# SX1268.net
KiCad netlist of a schematic drawn in Altium Designer
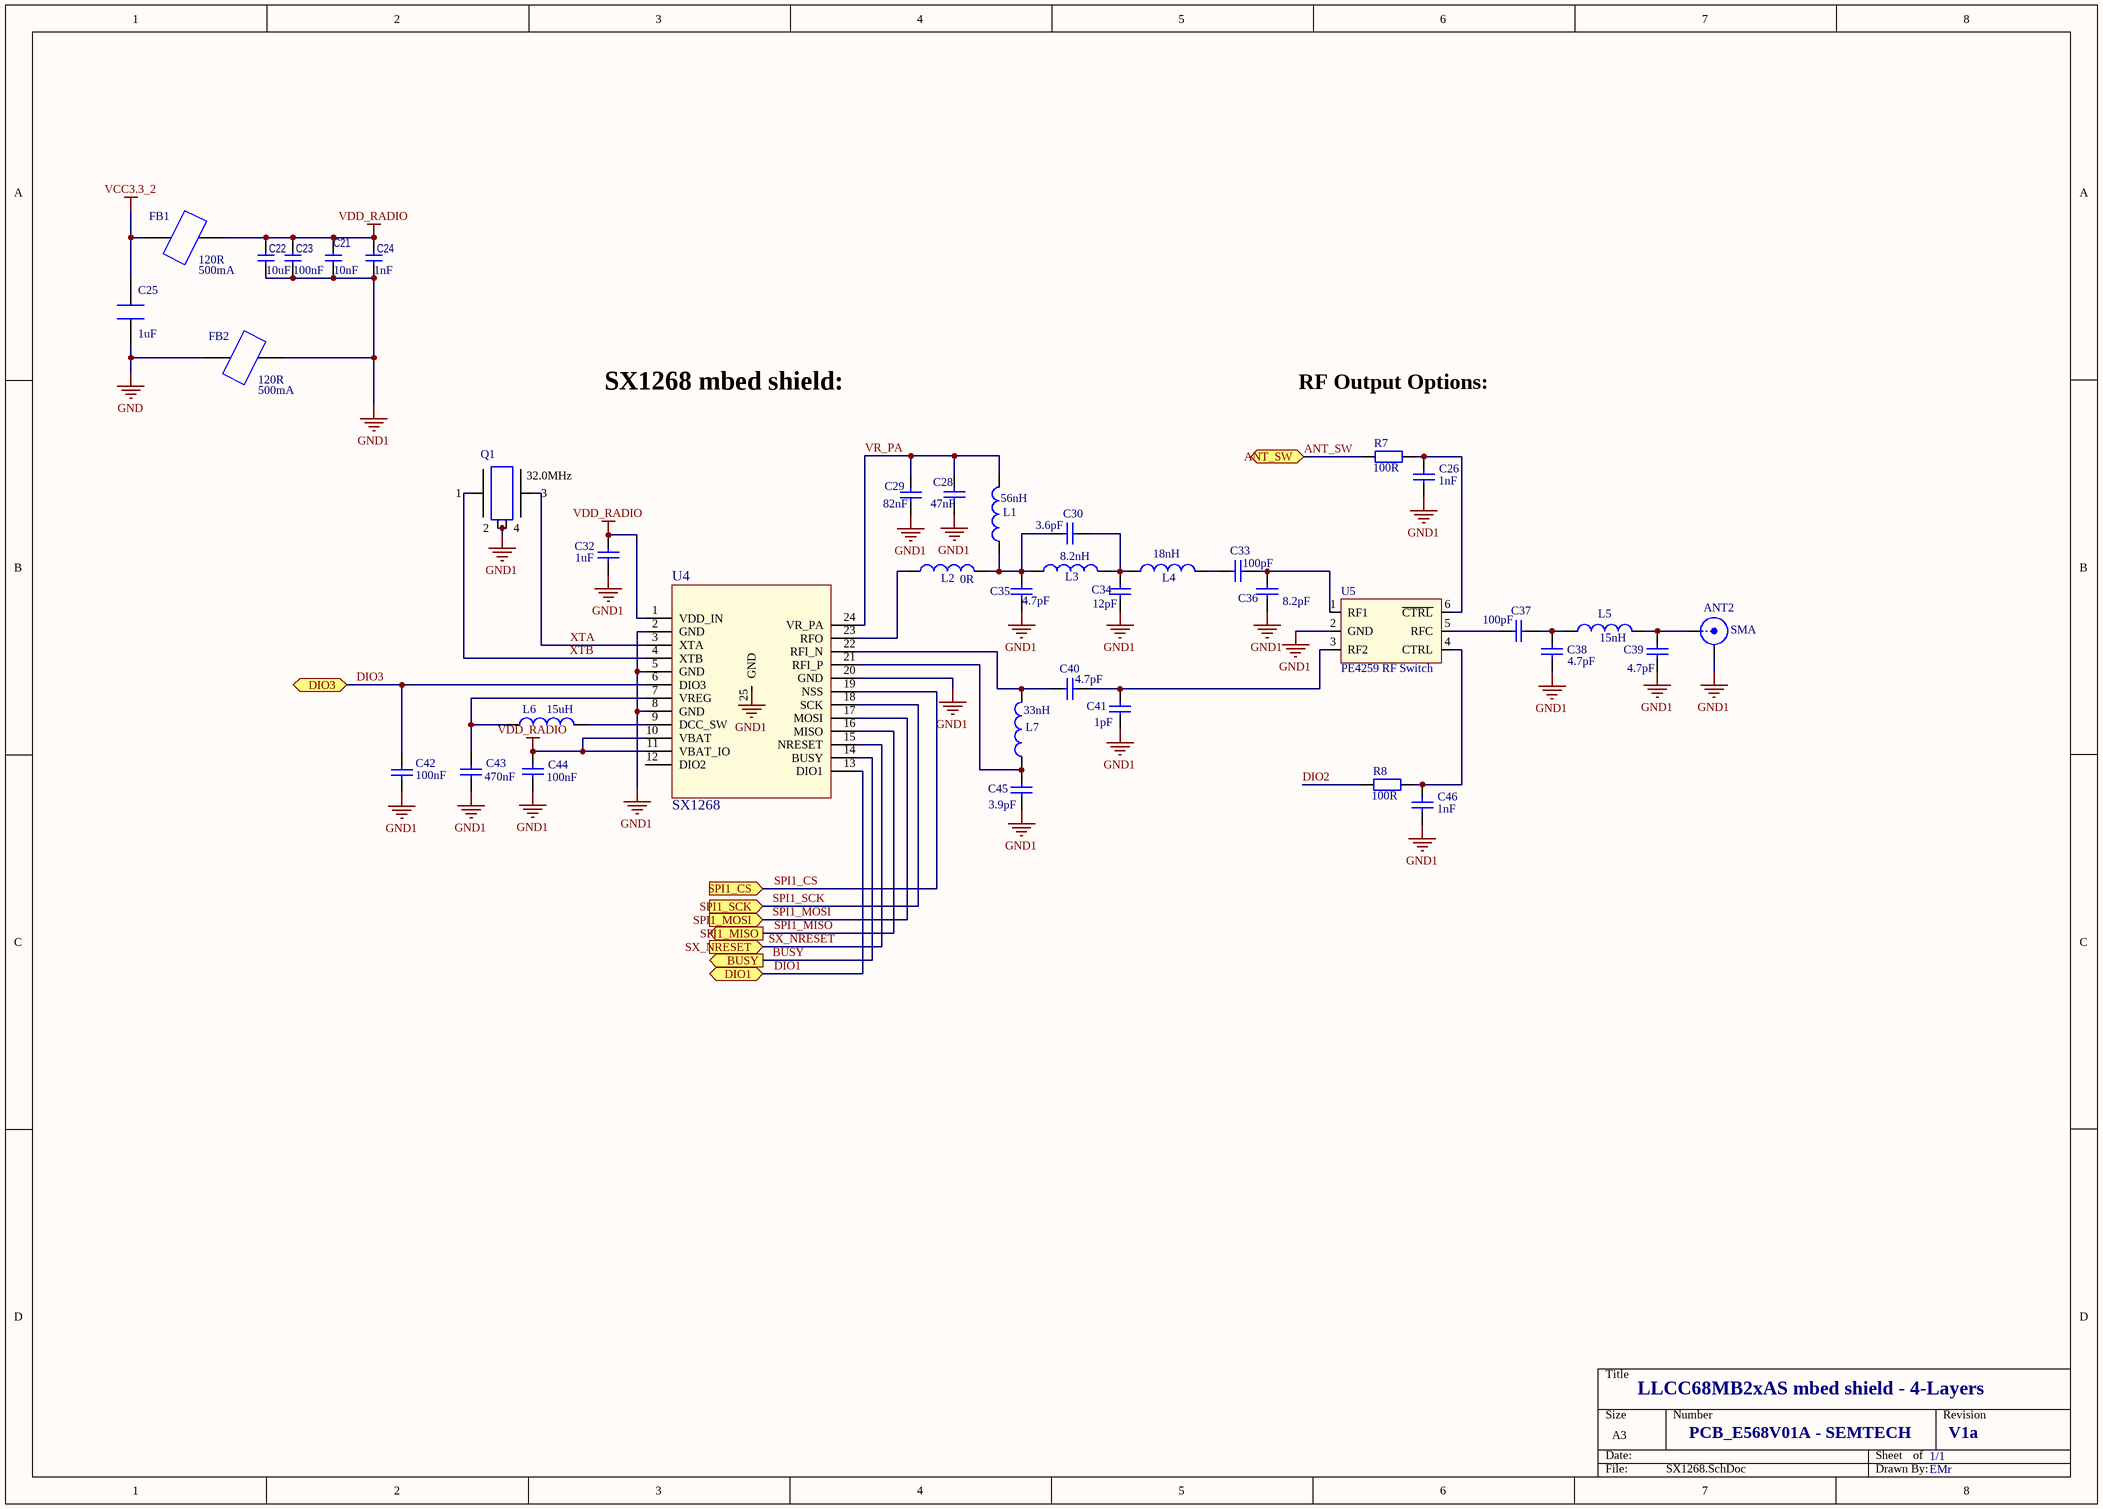
[diagram p0: SX1268.SchDoc]

(export (version "E")
  (design (tool "Eeschema 10.0.6"))
  (components
    (comp (ref "ANT2")
      (value "SMA")
      (footprint "SMA_end_launch_1.0mm_9.52mm")
      (description "SMA Straight Connector")
      (fields (field (name "PUBLISHER") "Altium Limited"))
      (libsource (lib "SX1262MB2xAS_e499v01b") (part "SMA"))
    )
    (comp (ref "C21")
      (value "10nF")
      (footprint "rlc_402_smd")
      (libsource (lib "baseboard") (part "ProE.tmp_22p_13"))
    )
    (comp (ref "C22")
      (value "10uF")
      (footprint "rlc_402_smd")
      (libsource (lib "baseboard") (part "ProE.tmp_22p_13"))
    )
    (comp (ref "C23")
      (value "100nF")
      (footprint "rlc_402_smd")
      (libsource (lib "baseboard") (part "ProE.tmp_22p_13"))
    )
    (comp (ref "C24")
      (value "1nF")
      (footprint "rlc_402_smd")
      (libsource (lib "baseboard") (part "ProE.tmp_22p_13"))
    )
    (comp (ref "C25")
      (value "1uF")
      (footprint "rlc_402_smd")
      (description "MLCC 4.7uF 0805 X5R 10V")
      (fields
        (field (name "XMOS PART NUMBER") "E-02-0021")
        (field (name "MANUFACTURER") "Murata")
        (field (name "PART CREATOR") "JG")
        (field (name "APPROVED") "NO")
      )
      (libsource (lib "XMOS_Alt_Lib") (part "CAP_NP"))
    )
    (comp (ref "C26")
      (value "1nF")
      (footprint "rlc_402_smd")
      (description "Capacitor SMD")
      (fields (field (name "PUBLISHER") "Altium Limited"))
      (libsource (lib "SX1262MB2xAS_e499v01b") (part "Cap"))
    )
    (comp (ref "C28")
      (value "47nF")
      (footprint "rlc_402_smd")
      (description "Capacitor SMD")
      (fields (field (name "PUBLISHER") "Altium Limited"))
      (libsource (lib "SX1262MB2xAS_e499v01b") (part "Cap"))
    )
    (comp (ref "C29")
      (value "82nF")
      (footprint "rlc_402_smd")
      (description "Capacitor SMD")
      (fields (field (name "PUBLISHER") "Altium Limited"))
      (libsource (lib "SX1262MB2xAS_e499v01b") (part "Cap"))
    )
    (comp (ref "C30")
      (value "3.6pF")
      (footprint "rlc_402_smd")
      (description "Capacitor SMD")
      (fields (field (name "PUBLISHER") "Altium Limited"))
      (libsource (lib "SX1262MB2xAS_e499v01b") (part "Cap"))
    )
    (comp (ref "C32")
      (value "1uF")
      (footprint "rlc_402_smd")
      (description "Capacitor SMD")
      (fields (field (name "PUBLISHER") "Altium Limited"))
      (libsource (lib "SX1262MB2xAS_e499v01b") (part "Cap"))
    )
    (comp (ref "C33")
      (value "100pF")
      (footprint "rlc_402_smd")
      (description "Capacitor SMD")
      (fields (field (name "PUBLISHER") "Altium Limited"))
      (libsource (lib "SX1262MB2xAS_e499v01b") (part "Cap"))
    )
    (comp (ref "C34")
      (value "12pF")
      (footprint "rlc_402_smd")
      (description "Capacitor SMD")
      (fields (field (name "PUBLISHER") "Altium Limited"))
      (libsource (lib "SX1262MB2xAS_e499v01b") (part "Cap"))
    )
    (comp (ref "C35")
      (value "4.7pF")
      (footprint "rlc_402_smd")
      (description "Capacitor SMD")
      (fields (field (name "PUBLISHER") "Altium Limited"))
      (libsource (lib "SX1262MB2xAS_e499v01b") (part "Cap"))
    )
    (comp (ref "C36")
      (value "8.2pF")
      (footprint "rlc_402_smd")
      (description "Capacitor SMD")
      (fields (field (name "PUBLISHER") "Altium Limited"))
      (libsource (lib "SX1262MB2xAS_e499v01b") (part "Cap"))
    )
    (comp (ref "C37")
      (value "100pF")
      (footprint "rlc_402_smd")
      (description "Capacitor SMD")
      (fields (field (name "PUBLISHER") "Altium Limited"))
      (libsource (lib "SX1262MB2xAS_e499v01b") (part "Cap"))
    )
    (comp (ref "C38")
      (value "4.7pF")
      (footprint "rlc_402_smd")
      (description "Capacitor SMD")
      (fields (field (name "PUBLISHER") "Altium Limited"))
      (libsource (lib "SX1262MB2xAS_e499v01b") (part "Cap"))
    )
    (comp (ref "C39")
      (value "4.7pF")
      (footprint "rlc_402_smd")
      (description "Capacitor SMD")
      (fields (field (name "PUBLISHER") "Altium Limited"))
      (libsource (lib "SX1262MB2xAS_e499v01b") (part "Cap"))
    )
    (comp (ref "C40")
      (value "4.7pF")
      (footprint "rlc_402_smd")
      (description "Capacitor SMD")
      (fields (field (name "PUBLISHER") "Altium Limited"))
      (libsource (lib "SX1262MB2xAS_e499v01b") (part "Cap"))
    )
    (comp (ref "C41")
      (value "1pF")
      (footprint "rlc_402_smd")
      (description "Capacitor SMD")
      (fields (field (name "PUBLISHER") "Altium Limited"))
      (libsource (lib "SX1262MB2xAS_e499v01b") (part "Cap"))
    )
    (comp (ref "C42")
      (value "100nF")
      (footprint "rlc_402_smd")
      (description "Capacitor SMD")
      (fields (field (name "PUBLISHER") "Altium Limited"))
      (libsource (lib "LLCC68MB2xAS_e568v01a") (part "Cap"))
    )
    (comp (ref "C43")
      (value "470nF")
      (footprint "rlc_402_smd")
      (description "Capacitor SMD")
      (fields (field (name "PUBLISHER") "Altium Limited"))
      (libsource (lib "SX1262MB2xAS_e499v01b") (part "Cap"))
    )
    (comp (ref "C44")
      (value "100nF")
      (footprint "rlc_402_smd")
      (description "Capacitor SMD")
      (fields (field (name "PUBLISHER") "Altium Limited"))
      (libsource (lib "SX1262MB2xAS_e499v01b") (part "Cap"))
    )
    (comp (ref "C45")
      (value "3.9pF")
      (footprint "rlc_402_smd")
      (description "Capacitor SMD")
      (fields (field (name "PUBLISHER") "Altium Limited"))
      (libsource (lib "SX1262MB2xAS_e499v01b") (part "Cap"))
    )
    (comp (ref "C46")
      (value "1nF")
      (footprint "rlc_402_smd")
      (description "Capacitor SMD")
      (fields (field (name "PUBLISHER") "Altium Limited"))
      (libsource (lib "SX1262MB2xAS_e499v01b") (part "Cap"))
    )
    (comp (ref "FB1")
      (value "120R")
      (footprint "R0603")
      (description "Ferrite Bead, 120R AT 100MHz, 0603, 500mA")
      (fields
        (field (name "XMOS PART NUMBER") "E-08-0007")
        (field (name "RATED CURRENT") "500mA")
        (field (name "MANUFACTURER") "Murata")
        (field (name "PART CREATOR") "JG")
        (field (name "APPROVED") "NO")
      )
      (libsource (lib "XMOS_Alt_Lib") (part "FERRITE"))
    )
    (comp (ref "FB2")
      (value "120R")
      (footprint "R0603")
      (description "Ferrite Bead, 120R AT 100MHz, 0603, 500mA")
      (fields
        (field (name "XMOS PART NUMBER") "E-08-0007")
        (field (name "RATED CURRENT") "500mA")
        (field (name "MANUFACTURER") "Murata")
        (field (name "PART CREATOR") "JG")
        (field (name "APPROVED") "NO")
      )
      (libsource (lib "XMOS_Alt_Lib") (part "FERRITE"))
    )
    (comp (ref "L1")
      (value "56nH")
      (footprint "rlc_402_smd")
      (description "Inductor SMD")
      (fields (field (name "PUBLISHER") "Altium Limited"))
      (libsource (lib "SX1262MB2xAS_e499v01b") (part "Inductor"))
    )
    (comp (ref "L2")
      (value "0R")
      (footprint "rlc_402_smd")
      (description "Inductor SMD")
      (fields (field (name "PUBLISHER") "Altium Limited"))
      (libsource (lib "SX1262MB2xAS_e499v01b") (part "Inductor"))
    )
    (comp (ref "L3")
      (value "8.2nH")
      (footprint "rlc_402_smd")
      (description "Inductor SMD")
      (fields (field (name "PUBLISHER") "Altium Limited"))
      (libsource (lib "SX1262MB2xAS_e499v01b") (part "Inductor"))
    )
    (comp (ref "L4")
      (value "18nH")
      (footprint "rlc_402_smd")
      (description "Inductor SMD")
      (fields (field (name "PUBLISHER") "Altium Limited"))
      (libsource (lib "SX1262MB2xAS_e499v01b") (part "Inductor"))
    )
    (comp (ref "L5")
      (value "15nH")
      (footprint "rlc_402_smd")
      (description "Inductor SMD")
      (fields (field (name "PUBLISHER") "Altium Limited"))
      (libsource (lib "SX1262MB2xAS_e499v01b") (part "Inductor"))
    )
    (comp (ref "L6")
      (value "15uH")
      (footprint "rlc_805_smd enlarged")
      (description "Inductor SMD")
      (fields (field (name "PUBLISHER") "Altium Limited"))
      (libsource (lib "SX1262MB2xAS_e499v01b") (part "Inductor"))
    )
    (comp (ref "L7")
      (value "33nH")
      (footprint "rlc_402_smd")
      (description "Inductor SMD")
      (fields (field (name "PUBLISHER") "Altium Limited"))
      (libsource (lib "SX1262MB2xAS_e499v01b") (part "Inductor"))
    )
    (comp (ref "Q1")
      (value "32.0MHz")
      (footprint "nd2016da")
      (description "Crystal with GND pins")
      (fields (field (name "Comment") "32MHz"))
      (libsource (lib "SX1262MB2xAS_e499v01b") (part "Xtal GND"))
    )
    (comp (ref "R7")
      (value "100R")
      (footprint "rlc_402_smd")
      (description "Resistor SMD - IEC symbol version")
      (libsource (lib "SX1262MB2xAS_e499v01b") (part "Resistor"))
    )
    (comp (ref "R8")
      (value "100R")
      (footprint "rlc_402_smd")
      (description "Resistor SMD - IEC symbol version")
      (libsource (lib "SX1262MB2xAS_e499v01b") (part "Resistor"))
    )
    (comp (ref "U4")
      (value "SX1268")
      (footprint "vqfn24_4x4mm - duplicate")
      (description "SX1262- Ultra low power RF transceiver")
      (libsource (lib "SX1262MB2xAS_e499v01b") (part "SX126x"))
    )
    (comp (ref "U5")
      (value "PE4259 RF Switch")
      (footprint "SC70-6")
      (description "PE4259 Peregrine RF Switch")
      (libsource (lib "SX1262MB2xAS_e499v01b") (part "PE4259 RF Switch"))
    )
  )
  (nets
    (net (code "1") (name "/ANT_SW") (class "Default")
      (node (ref "R7") (pin "2") (pinfunction "2_2") (pintype "passive"))
    )
    (net (code "2") (name "/BUSY") (class "Default")
      (node (ref "U4") (pin "14") (pinfunction "BUSY_14") (pintype "passive"))
    )
    (net (code "3") (name "/DIO1") (class "Default")
      (node (ref "U4") (pin "13") (pinfunction "DIO1_13") (pintype "passive"))
    )
    (net (code "4") (name "/DIO2") (class "Default")
      (node (ref "R8") (pin "2") (pinfunction "2_2") (pintype "passive"))
    )
    (net (code "5") (name "/DIO3") (class "Default")
      (node (ref "C42") (pin "2") (pinfunction "2_2") (pintype "passive"))
      (node (ref "U4") (pin "6") (pinfunction "DIO3_6") (pintype "passive"))
    )
    (net (code "6") (name "/SPI1_CS") (class "Default")
      (node (ref "U4") (pin "19") (pinfunction "NSS_19") (pintype "passive"))
    )
    (net (code "7") (name "/SPI1_MISO") (class "Default")
      (node (ref "U4") (pin "16") (pinfunction "MISO_16") (pintype "passive"))
    )
    (net (code "8") (name "/SPI1_MOSI") (class "Default")
      (node (ref "U4") (pin "17") (pinfunction "MOSI_17") (pintype "passive"))
    )
    (net (code "9") (name "/SPI1_SCK") (class "Default")
      (node (ref "U4") (pin "18") (pinfunction "SCK_18") (pintype "passive"))
    )
    (net (code "10") (name "/SX_NRESET") (class "Default")
      (node (ref "U4") (pin "15") (pinfunction "NRESET_15") (pintype "passive"))
    )
    (net (code "11") (name "/VR_PA") (class "Default")
      (node (ref "C28") (pin "2") (pinfunction "2_2") (pintype "passive"))
      (node (ref "C29") (pin "2") (pinfunction "2_2") (pintype "passive"))
      (node (ref "L1") (pin "2") (pinfunction "2_2") (pintype "passive"))
      (node (ref "U4") (pin "24") (pinfunction "VR_PA_24") (pintype "power_in"))
    )
    (net (code "12") (name "/XTA") (class "Default")
      (node (ref "Q1") (pin "3") (pinfunction "3_3") (pintype "passive"))
      (node (ref "U4") (pin "3") (pinfunction "XTA_3") (pintype "passive"))
    )
    (net (code "14") (name "/XTB") (class "Default")
      (node (ref "Q1") (pin "1") (pinfunction "1_1") (pintype "passive"))
      (node (ref "U4") (pin "4") (pinfunction "XTB_4") (pintype "passive"))
    )
    (net (code "15") (name "GND") (class "Default")
      (node (ref "C25") (pin "2") (pinfunction "T2_2") (pintype "passive"))
      (node (ref "FB2") (pin "1") (pinfunction "P1_1") (pintype "passive"))
    )
    (net (code "16") (name "GND1") (class "Default")
      (node (ref "ANT2") (pin "2") (pinfunction "GND_2") (pintype "passive"))
      (node (ref "C21") (pin "2") (pintype "passive"))
      (node (ref "C22") (pin "2") (pintype "passive"))
      (node (ref "C23") (pin "2") (pintype "passive"))
      (node (ref "C24") (pin "2") (pintype "passive"))
      (node (ref "C26") (pin "2") (pinfunction "2_2") (pintype "passive"))
      (node (ref "C28") (pin "1") (pinfunction "1_1") (pintype "passive"))
      (node (ref "C29") (pin "1") (pinfunction "1_1") (pintype "passive"))
      (node (ref "C32") (pin "1") (pinfunction "1_1") (pintype "passive"))
      (node (ref "C34") (pin "1") (pinfunction "1_1") (pintype "passive"))
      (node (ref "C35") (pin "1") (pinfunction "1_1") (pintype "passive"))
      (node (ref "C36") (pin "1") (pinfunction "1_1") (pintype "passive"))
      (node (ref "C38") (pin "1") (pinfunction "1_1") (pintype "passive"))
      (node (ref "C39") (pin "1") (pinfunction "1_1") (pintype "passive"))
      (node (ref "C41") (pin "1") (pinfunction "1_1") (pintype "passive"))
      (node (ref "C42") (pin "1") (pinfunction "1_1") (pintype "passive"))
      (node (ref "C43") (pin "1") (pinfunction "1_1") (pintype "passive"))
      (node (ref "C44") (pin "1") (pinfunction "1_1") (pintype "passive"))
      (node (ref "C45") (pin "1") (pinfunction "1_1") (pintype "passive"))
      (node (ref "C46") (pin "2") (pinfunction "2_2") (pintype "passive"))
      (node (ref "FB2") (pin "2") (pinfunction "P2_2") (pintype "passive"))
      (node (ref "Q1") (pin "2") (pinfunction "2_2") (pintype "passive"))
      (node (ref "Q1") (pin "4") (pinfunction "4_4") (pintype "passive"))
      (node (ref "U4") (pin "2") (pinfunction "GND_2") (pintype "passive"))
      (node (ref "U4") (pin "20") (pinfunction "GND_20") (pintype "passive"))
      (node (ref "U4") (pin "25") (pinfunction "GND_25") (pintype "passive"))
      (node (ref "U4") (pin "5") (pinfunction "GND_5") (pintype "passive"))
      (node (ref "U4") (pin "8") (pinfunction "GND_8") (pintype "passive"))
      (node (ref "U5") (pin "2") (pinfunction "GND_2") (pintype "passive"))
    )
    (net (code "17") (name "Net-(ANT2-Signal)") (class "Default")
      (node (ref "ANT2") (pin "1") (pinfunction "Signal_1") (pintype "passive"))
      (node (ref "C39") (pin "2") (pinfunction "2_2") (pintype "passive"))
      (node (ref "L5") (pin "2") (pinfunction "2_2") (pintype "passive"))
    )
    (net (code "18") (name "Net-(C30-Pad1)") (class "Default")
      (node (ref "C30") (pin "1") (pinfunction "1_1") (pintype "passive"))
      (node (ref "C34") (pin "2") (pinfunction "2_2") (pintype "passive"))
      (node (ref "L3") (pin "2") (pinfunction "2_2") (pintype "passive"))
      (node (ref "L4") (pin "1") (pinfunction "1_1") (pintype "passive"))
    )
    (net (code "19") (name "Net-(C30-Pad2)") (class "Default")
      (node (ref "C30") (pin "2") (pinfunction "2_2") (pintype "passive"))
      (node (ref "C35") (pin "2") (pinfunction "2_2") (pintype "passive"))
      (node (ref "L1") (pin "1") (pinfunction "1_1") (pintype "passive"))
      (node (ref "L2") (pin "2") (pinfunction "2_2") (pintype "passive"))
      (node (ref "L3") (pin "1") (pinfunction "1_1") (pintype "passive"))
    )
    (net (code "20") (name "Net-(C33-Pad2)") (class "Default")
      (node (ref "C33") (pin "2") (pinfunction "2_2") (pintype "passive"))
      (node (ref "L4") (pin "2") (pinfunction "2_2") (pintype "passive"))
    )
    (net (code "21") (name "Net-(C37-Pad1)") (class "Default")
      (node (ref "C37") (pin "1") (pinfunction "1_1") (pintype "passive"))
      (node (ref "C38") (pin "2") (pinfunction "2_2") (pintype "passive"))
      (node (ref "L5") (pin "1") (pinfunction "1_1") (pintype "passive"))
    )
    (net (code "22") (name "Net-(U4-DCC_SW)") (class "Default")
      (node (ref "L6") (pin "2") (pinfunction "2_2") (pintype "passive"))
      (node (ref "U4") (pin "9") (pinfunction "DCC_SW_9") (pintype "power_in"))
    )
    (net (code "23") (name "Net-(U4-RFI_N)") (class "Default")
      (node (ref "C40") (pin "2") (pinfunction "2_2") (pintype "passive"))
      (node (ref "L7") (pin "2") (pinfunction "2_2") (pintype "passive"))
      (node (ref "U4") (pin "22") (pinfunction "RFI_N_22") (pintype "passive"))
    )
    (net (code "24") (name "Net-(U4-RFI_P)") (class "Default")
      (node (ref "C45") (pin "2") (pinfunction "2_2") (pintype "passive"))
      (node (ref "L7") (pin "1") (pinfunction "1_1") (pintype "passive"))
      (node (ref "U4") (pin "21") (pinfunction "RFI_P_21") (pintype "passive"))
    )
    (net (code "25") (name "Net-(U4-RFO)") (class "Default")
      (node (ref "L2") (pin "1") (pinfunction "1_1") (pintype "passive"))
      (node (ref "U4") (pin "23") (pinfunction "RFO_23") (pintype "passive"))
    )
    (net (code "26") (name "Net-(U4-VREG)") (class "Default")
      (node (ref "C43") (pin "2") (pinfunction "2_2") (pintype "passive"))
      (node (ref "L6") (pin "1") (pinfunction "1_1") (pintype "passive"))
      (node (ref "U4") (pin "7") (pinfunction "VREG_7") (pintype "power_in"))
    )
    (net (code "27") (name "Net-(U5-CTRL)") (class "Default")
      (node (ref "C46") (pin "1") (pinfunction "1_1") (pintype "passive"))
      (node (ref "R8") (pin "1") (pinfunction "1_1") (pintype "passive"))
      (node (ref "U5") (pin "4") (pinfunction "CTRL_4") (pintype "passive"))
    )
    (net (code "28") (name "Net-(U5-RF1)") (class "Default")
      (node (ref "C33") (pin "1") (pinfunction "1_1") (pintype "passive"))
      (node (ref "C36") (pin "2") (pinfunction "2_2") (pintype "passive"))
      (node (ref "U5") (pin "1") (pinfunction "RF1_1") (pintype "passive"))
    )
    (net (code "29") (name "Net-(U5-RF2)") (class "Default")
      (node (ref "C40") (pin "1") (pinfunction "1_1") (pintype "passive"))
      (node (ref "C41") (pin "2") (pinfunction "2_2") (pintype "passive"))
      (node (ref "U5") (pin "3") (pinfunction "RF2_3") (pintype "passive"))
    )
    (net (code "30") (name "Net-(U5-RFC)") (class "Default")
      (node (ref "C37") (pin "2") (pinfunction "2_2") (pintype "passive"))
      (node (ref "U5") (pin "5") (pinfunction "RFC_5") (pintype "passive"))
    )
    (net (code "31") (name "Net-(U5-~{CTRL})") (class "Default")
      (node (ref "C26") (pin "1") (pinfunction "1_1") (pintype "passive"))
      (node (ref "R7") (pin "1") (pinfunction "1_1") (pintype "passive"))
      (node (ref "U5") (pin "6") (pinfunction "~{CTRL}_6") (pintype "passive"))
    )
    (net (code "32") (name "VCC3.3_2") (class "Default")
      (node (ref "C25") (pin "1") (pinfunction "T1_1") (pintype "passive"))
      (node (ref "FB1") (pin "1") (pinfunction "P1_1") (pintype "passive"))
    )
    (net (code "33") (name "VDD_RADIO") (class "Default")
      (node (ref "C21") (pin "1") (pintype "passive"))
      (node (ref "C22") (pin "1") (pintype "passive"))
      (node (ref "C23") (pin "1") (pintype "passive"))
      (node (ref "C24") (pin "1") (pintype "passive"))
      (node (ref "C32") (pin "2") (pinfunction "2_2") (pintype "passive"))
      (node (ref "C44") (pin "2") (pinfunction "2_2") (pintype "passive"))
      (node (ref "FB1") (pin "2") (pinfunction "P2_2") (pintype "passive"))
      (node (ref "U4") (pin "1") (pinfunction "VDD_IN_1") (pintype "power_in"))
      (node (ref "U4") (pin "10") (pinfunction "VBAT_10") (pintype "power_in"))
      (node (ref "U4") (pin "11") (pinfunction "VBAT_IO_11") (pintype "power_in"))
    )
    (net (code "34") (name "unconnected-(U4-DIO2-Pad12)") (class "Default")
      (node (ref "U4") (pin "12") (pinfunction "DIO2_12") (pintype "passive"))
    )
  )
)
